# four_neopixels.net
KiCad netlist of a schematic drawn in Altium Designer
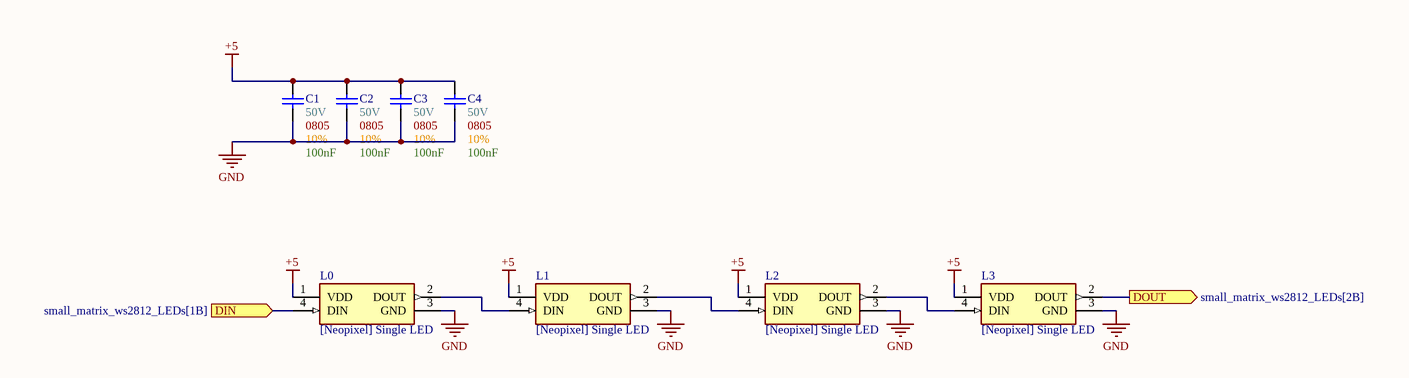
[diagram p0: four_neopixels.SchDoc]

(export (version "E")
  (design (tool "Eeschema 10.0.6"))
  (components
    (comp (ref "C1")
      (value "[Cap] 0805 0.1uF 10% 50V")
      (footprint "[Cap] SMD 0805")
      (description "CL21B104KBCNNNC")
      (fields
        (field (name "MAX VOLTAGE") "50V")
        (field (name "SIZE PACKAGE") "0805")
        (field (name "TOLERANCE") "10%")
        (field (name "CAPACITANCE") "100nF")
      )
      (libsource (lib "Capacitors") (part "[Cap] 0805 0.1uF 10% 50V"))
    )
    (comp (ref "C2")
      (value "[Cap] 0805 0.1uF 10% 50V")
      (footprint "[Cap] SMD 0805")
      (description "CL21B104KBCNNNC")
      (fields
        (field (name "MAX VOLTAGE") "50V")
        (field (name "SIZE PACKAGE") "0805")
        (field (name "TOLERANCE") "10%")
        (field (name "CAPACITANCE") "100nF")
      )
      (libsource (lib "Capacitors") (part "[Cap] 0805 0.1uF 10% 50V"))
    )
    (comp (ref "C3")
      (value "[Cap] 0805 0.1uF 10% 50V")
      (footprint "[Cap] SMD 0805")
      (description "CL21B104KBCNNNC")
      (fields
        (field (name "MAX VOLTAGE") "50V")
        (field (name "SIZE PACKAGE") "0805")
        (field (name "TOLERANCE") "10%")
        (field (name "CAPACITANCE") "100nF")
      )
      (libsource (lib "Capacitors") (part "[Cap] 0805 0.1uF 10% 50V"))
    )
    (comp (ref "C4")
      (value "[Cap] 0805 0.1uF 10% 50V")
      (footprint "[Cap] SMD 0805")
      (description "CL21B104KBCNNNC")
      (fields
        (field (name "MAX VOLTAGE") "50V")
        (field (name "SIZE PACKAGE") "0805")
        (field (name "TOLERANCE") "10%")
        (field (name "CAPACITANCE") "100nF")
      )
      (libsource (lib "Capacitors") (part "[Cap] 0805 0.1uF 10% 50V"))
    )
    (comp (ref "L0")
      (value "[Neopixel] Single LED")
      (footprint "[Neopixel] Single LED")
      (description "WS2812B")
      (libsource (lib "LEDs") (part "[Neopixel] Single LED"))
    )
    (comp (ref "L1")
      (value "[Neopixel] Single LED")
      (footprint "[Neopixel] Single LED")
      (description "WS2812B")
      (libsource (lib "LEDs") (part "[Neopixel] Single LED"))
    )
    (comp (ref "L2")
      (value "[Neopixel] Single LED")
      (footprint "[Neopixel] Single LED")
      (description "WS2812B")
      (libsource (lib "LEDs") (part "[Neopixel] Single LED"))
    )
    (comp (ref "L3")
      (value "[Neopixel] Single LED")
      (footprint "[Neopixel] Single LED")
      (description "WS2812B")
      (libsource (lib "LEDs") (part "[Neopixel] Single LED"))
    )
  )
  (nets
    (net (code "1") (name "+5") (class "Default")
      (node (ref "C1") (pin "2") (pinfunction "2_2") (pintype "passive"))
      (node (ref "C2") (pin "2") (pinfunction "2_2") (pintype "passive"))
      (node (ref "C3") (pin "2") (pinfunction "2_2") (pintype "passive"))
      (node (ref "C4") (pin "2") (pinfunction "2_2") (pintype "passive"))
      (node (ref "L0") (pin "1") (pinfunction "VDD_1") (pintype "power_in"))
      (node (ref "L1") (pin "1") (pinfunction "VDD_1") (pintype "power_in"))
      (node (ref "L2") (pin "1") (pinfunction "VDD_1") (pintype "power_in"))
      (node (ref "L3") (pin "1") (pinfunction "VDD_1") (pintype "power_in"))
    )
    (net (code "2") (name "/DIN") (class "Default")
      (node (ref "L0") (pin "4") (pinfunction "DIN_4") (pintype "input"))
    )
    (net (code "3") (name "/DOUT") (class "Default")
      (node (ref "L3") (pin "2") (pinfunction "DOUT_2") (pintype "output"))
    )
    (net (code "4") (name "GND") (class "Default")
      (node (ref "C1") (pin "1") (pinfunction "1_1") (pintype "passive"))
      (node (ref "C2") (pin "1") (pinfunction "1_1") (pintype "passive"))
      (node (ref "C3") (pin "1") (pinfunction "1_1") (pintype "passive"))
      (node (ref "C4") (pin "1") (pinfunction "1_1") (pintype "passive"))
      (node (ref "L0") (pin "3") (pinfunction "GND_3") (pintype "power_in"))
      (node (ref "L1") (pin "3") (pinfunction "GND_3") (pintype "power_in"))
      (node (ref "L2") (pin "3") (pinfunction "GND_3") (pintype "power_in"))
      (node (ref "L3") (pin "3") (pinfunction "GND_3") (pintype "power_in"))
    )
    (net (code "5") (name "Net-(L0-DOUT)") (class "Default")
      (node (ref "L0") (pin "2") (pinfunction "DOUT_2") (pintype "output"))
      (node (ref "L1") (pin "4") (pinfunction "DIN_4") (pintype "input"))
    )
    (net (code "6") (name "Net-(L1-DOUT)") (class "Default")
      (node (ref "L1") (pin "2") (pinfunction "DOUT_2") (pintype "output"))
      (node (ref "L2") (pin "4") (pinfunction "DIN_4") (pintype "input"))
    )
    (net (code "7") (name "Net-(L2-DOUT)") (class "Default")
      (node (ref "L2") (pin "2") (pinfunction "DOUT_2") (pintype "output"))
      (node (ref "L3") (pin "4") (pinfunction "DIN_4") (pintype "input"))
    )
  )
)
